# SCH_PHOENIX_-_PCB-1.net
KiCad netlist of a schematic drawn in EasyEDA
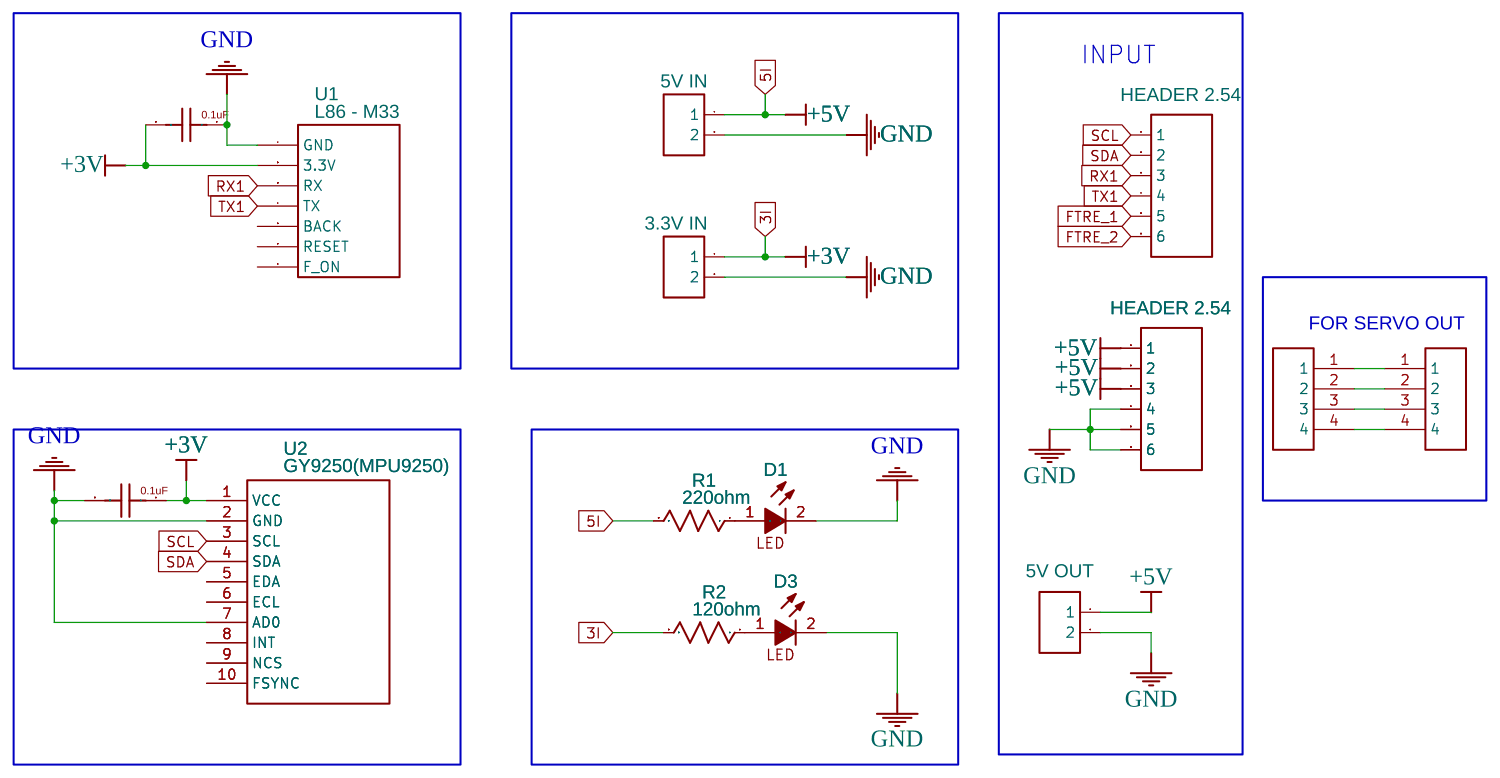
[diagram p0: schematic sheet]

(export (version "E")
  (design (tool "Eeschema 10.0.6"))
  (components
    (comp (ref "C1") (value "22PF CERAMIC CAPACITOR") (libsource (lib "") (part "22PF CERAMIC CAPACITOR")))
    (comp (ref "C4") (value "22PF CERAMIC CAPACITOR") (libsource (lib "") (part "22PF CERAMIC CAPACITOR_1")))
    (comp (ref "D1")
      (value "LED")
      (fields (field (name "Manufacturer Part") "5600") (field (name "Manufacturer") "VccLite"))
      (libsource (lib "") (part "LED"))
    )
    (comp (ref "D3")
      (value "LED")
      (fields (field (name "Manufacturer Part") "5600") (field (name "Manufacturer") "VccLite"))
      (libsource (lib "") (part "LED"))
    )
    (comp (ref "H1")
      (value "FOR SERVO OUT")
      (fields (field (name "Manufacturer Part") "2211S-04G") (field (name "Manufacturer") "MULTICOMP PRO"))
      (libsource (lib "") (part "B2B 2.54 MM HEADER_1"))
    )
    (comp (ref "H2")
      (value "FOR SERVO OUT")
      (fields (field (name "Manufacturer Part") "2211S-04G") (field (name "Manufacturer") "MULTICOMP PRO"))
      (libsource (lib "") (part "B2B 2.54 MM HEADER"))
    )
    (comp (ref "IN") (value "5V IN") (libsource (lib "") (part "CONN-TH_2P-P5.00")))
    (comp (ref "IN1") (value "5V OUT") (libsource (lib "") (part "CONN-TH_2P-P5.00")))
    (comp (ref "J1")
      (value "HEADER 2.54")
      (fields (field (name "Manufacturer Part") "2.54mm 1*20PHeader"))
      (libsource (lib "") (part "HEADER-MALE-2.54_1X6"))
    )
    (comp (ref "J2")
      (value "HEADER 2.54")
      (fields (field (name "Manufacturer Part") "2.54mm 1*20PHeader"))
      (libsource (lib "") (part "HEADER-MALE-2.54_1X6"))
    )
    (comp (ref "P1") (value "3.3V IN") (libsource (lib "") (part "CONN-TH_2P-P5.00_1")))
    (comp (ref "R1") (value "220ohm") (libsource (lib "") (part "R_0603_US")))
    (comp (ref "R2") (value "120ohm") (libsource (lib "") (part "R_0603_US")))
    (comp (ref "U1") (value "L86 - M33") (libsource (lib "") (part "BMP280 COPY")))
    (comp (ref "U2") (value "GY9250(MPU9250)") (libsource (lib "") (part "GY9250(MPU9250)")))
  )
  (nets
    (net (code "1") (name "3I") (class "Default")
      (node (ref "C1") (pin "2") (pinfunction "2_2") (pintype "unspecified"))
      (node (ref "C4") (pin "1") (pinfunction "1_1") (pintype "unspecified"))
      (node (ref "P1") (pin "1") (pinfunction "1_1") (pintype "unspecified"))
      (node (ref "R2") (pin "2") (pinfunction "2_2") (pintype "unspecified"))
      (node (ref "U1") (pin "6") (pinfunction "3.3V_6") (pintype "unspecified"))
      (node (ref "U2") (pin "1") (pinfunction "VCC_1") (pintype "unspecified"))
    )
    (net (code "2") (name "5I") (class "Default")
      (node (ref "IN") (pin "1") (pinfunction "1_1") (pintype "unspecified"))
      (node (ref "IN1") (pin "1") (pinfunction "1_1") (pintype "unspecified"))
      (node (ref "J2") (pin "1") (pinfunction "1_1") (pintype "input"))
      (node (ref "J2") (pin "2") (pinfunction "2_2") (pintype "input"))
      (node (ref "J2") (pin "3") (pinfunction "3_3") (pintype "input"))
      (node (ref "R1") (pin "2") (pinfunction "2_2") (pintype "unspecified"))
    )
    (net (code "3") (name "FTRE_1") (class "Default")
      (node (ref "J1") (pin "5") (pinfunction "5_5") (pintype "input"))
    )
    (net (code "4") (name "FTRE_2") (class "Default")
      (node (ref "J1") (pin "6") (pinfunction "6_6") (pintype "input"))
    )
    (net (code "5") (name "GND") (class "Default")
      (node (ref "C1") (pin "1") (pinfunction "1_1") (pintype "unspecified"))
      (node (ref "C4") (pin "2") (pinfunction "2_2") (pintype "unspecified"))
      (node (ref "D1") (pin "2") (pinfunction "K_2") (pintype "unspecified"))
      (node (ref "D3") (pin "2") (pinfunction "K_2") (pintype "unspecified"))
      (node (ref "IN") (pin "2") (pinfunction "2_2") (pintype "unspecified"))
      (node (ref "IN1") (pin "2") (pinfunction "2_2") (pintype "unspecified"))
      (node (ref "J2") (pin "4") (pinfunction "4_4") (pintype "input"))
      (node (ref "J2") (pin "5") (pinfunction "5_5") (pintype "input"))
      (node (ref "J2") (pin "6") (pinfunction "6_6") (pintype "input"))
      (node (ref "P1") (pin "2") (pinfunction "2_2") (pintype "unspecified"))
      (node (ref "U1") (pin "7") (pinfunction "GND_7") (pintype "unspecified"))
      (node (ref "U2") (pin "2") (pinfunction "GND_2") (pintype "unspecified"))
      (node (ref "U2") (pin "7") (pinfunction "AD0_7") (pintype "unspecified"))
    )
    (net (code "6") (name "Net-(D1-A)") (class "Default")
      (node (ref "D1") (pin "1") (pinfunction "A_1") (pintype "unspecified"))
      (node (ref "R1") (pin "1") (pinfunction "1_1") (pintype "unspecified"))
    )
    (net (code "7") (name "Net-(D3-A)") (class "Default")
      (node (ref "D3") (pin "1") (pinfunction "A_1") (pintype "unspecified"))
      (node (ref "R2") (pin "1") (pinfunction "1_1") (pintype "unspecified"))
    )
    (net (code "8") (name "Net-(H1-Pad1)") (class "Default")
      (node (ref "H1") (pin "1") (pinfunction "1_1") (pintype "unspecified"))
      (node (ref "H2") (pin "1") (pinfunction "1_1") (pintype "unspecified"))
    )
    (net (code "9") (name "Net-(H1-Pad2)") (class "Default")
      (node (ref "H1") (pin "2") (pinfunction "2_2") (pintype "unspecified"))
      (node (ref "H2") (pin "2") (pinfunction "2_2") (pintype "unspecified"))
    )
    (net (code "10") (name "Net-(H1-Pad3)") (class "Default")
      (node (ref "H1") (pin "3") (pinfunction "3_3") (pintype "unspecified"))
      (node (ref "H2") (pin "3") (pinfunction "3_3") (pintype "unspecified"))
    )
    (net (code "11") (name "Net-(H1-Pad4)") (class "Default")
      (node (ref "H1") (pin "4") (pinfunction "4_4") (pintype "unspecified"))
      (node (ref "H2") (pin "4") (pinfunction "4_4") (pintype "unspecified"))
    )
    (net (code "12") (name "RX1") (class "Default")
      (node (ref "J1") (pin "3") (pinfunction "3_3") (pintype "input"))
      (node (ref "U1") (pin "5") (pinfunction "RX_5") (pintype "unspecified"))
    )
    (net (code "13") (name "SCL") (class "Default")
      (node (ref "J1") (pin "1") (pinfunction "1_1") (pintype "input"))
      (node (ref "U2") (pin "3") (pinfunction "SCL_3") (pintype "unspecified"))
    )
    (net (code "14") (name "SDA") (class "Default")
      (node (ref "J1") (pin "2") (pinfunction "2_2") (pintype "input"))
      (node (ref "U2") (pin "4") (pinfunction "SDA_4") (pintype "unspecified"))
    )
    (net (code "15") (name "TX1") (class "Default")
      (node (ref "J1") (pin "4") (pinfunction "4_4") (pintype "input"))
      (node (ref "U1") (pin "4") (pinfunction "TX_4") (pintype "unspecified"))
    )
    (net (code "16") (name "unconnected-(U1-BACK-Pad3)") (class "Default")
      (node (ref "U1") (pin "3") (pinfunction "BACK_3") (pintype "unspecified"))
    )
    (net (code "17") (name "unconnected-(U1-F_ON-Pad1)") (class "Default")
      (node (ref "U1") (pin "1") (pinfunction "F_ON_1") (pintype "unspecified"))
    )
    (net (code "18") (name "unconnected-(U1-RESET-Pad2)") (class "Default")
      (node (ref "U1") (pin "2") (pinfunction "RESET_2") (pintype "unspecified"))
    )
    (net (code "19") (name "unconnected-(U2-ECL-Pad6)") (class "Default")
      (node (ref "U2") (pin "6") (pinfunction "ECL_6") (pintype "unspecified"))
    )
    (net (code "20") (name "unconnected-(U2-EDA-Pad5)") (class "Default")
      (node (ref "U2") (pin "5") (pinfunction "EDA_5") (pintype "unspecified"))
    )
    (net (code "21") (name "unconnected-(U2-FSYNC-Pad10)") (class "Default")
      (node (ref "U2") (pin "10") (pinfunction "FSYNC_10") (pintype "unspecified"))
    )
    (net (code "22") (name "unconnected-(U2-INT-Pad8)") (class "Default")
      (node (ref "U2") (pin "8") (pinfunction "INT_8") (pintype "unspecified"))
    )
    (net (code "23") (name "unconnected-(U2-NCS-Pad9)") (class "Default")
      (node (ref "U2") (pin "9") (pinfunction "NCS_9") (pintype "unspecified"))
    )
  )
)
